# 6_cell_amplifier.net
KiCad netlist of a schematic drawn in Altium Designer
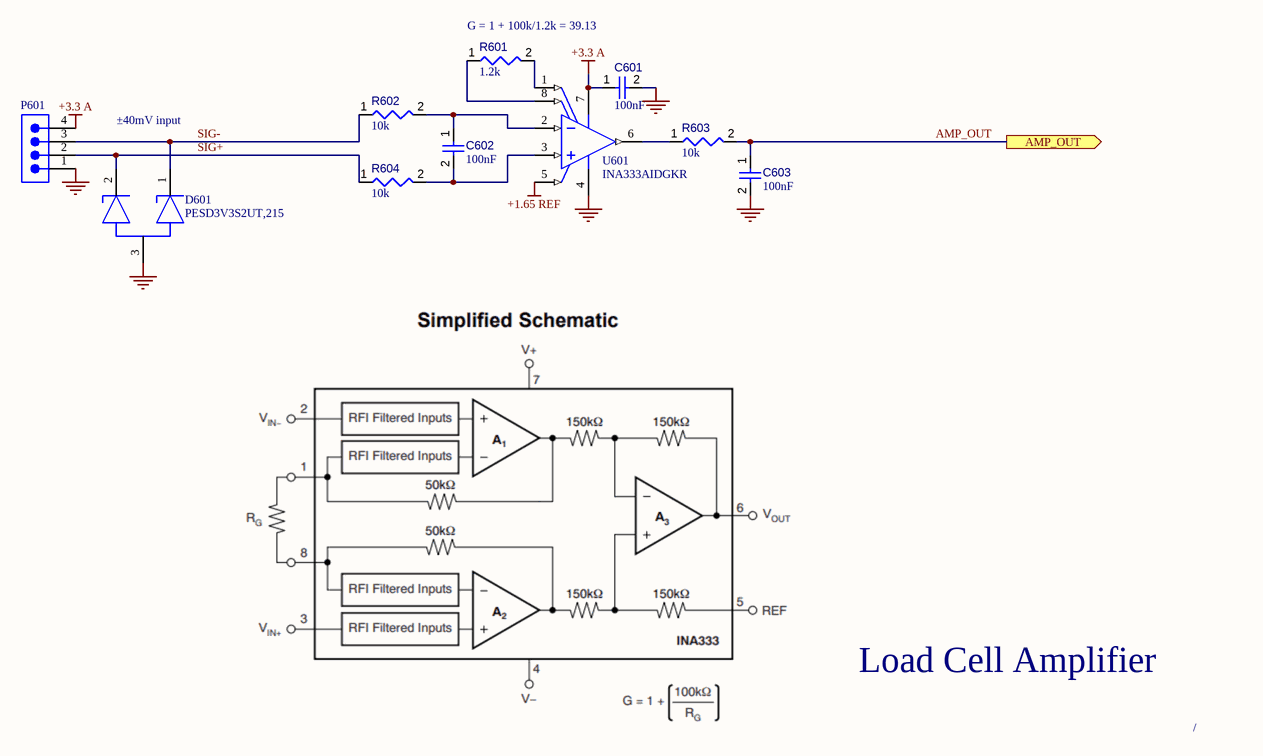
[diagram p0: 6 cell amplifier.SchDoc]

(export (version "E")
  (design (tool "Eeschema 10.0.6"))
  (components
    (comp (ref "C601")
      (value "100nF")
      (footprint "CAPC0402(1005)60_L")
      (description "Chip Capacitor, 100nF +/-20%, 25V, 0402, Thickness 0.6 mm")
      (fields (field (name "TOLERANCE") "10%") (field (name "Comment") "Capacitor 100nF +/-20% 25V 0402"))
      (libsource (lib "UBC Uncrewed Aircraft Systems") (part "CAP-NP-2"))
    )
    (comp (ref "C602")
      (value "100nF")
      (footprint "CAPC0402(1005)60_L")
      (description "Chip Capacitor, 100nF +/-20%, 25V, 0402, Thickness 0.6 mm")
      (fields (field (name "TOLERANCE") "10%") (field (name "Comment") "Capacitor 100nF +/-20% 25V 0402"))
      (libsource (lib "UBC Uncrewed Aircraft Systems") (part "CAP-NP-2"))
    )
    (comp (ref "C603")
      (value "100nF")
      (footprint "CAPC0402(1005)60_L")
      (description "Chip Capacitor, 100nF +/-20%, 25V, 0402, Thickness 0.6 mm")
      (fields (field (name "TOLERANCE") "10%") (field (name "Comment") "Capacitor 100nF +/-20% 25V 0402"))
      (libsource (lib "UBC Uncrewed Aircraft Systems") (part "CAP-NP-2"))
    )
    (comp (ref "D601")
      (value "PESD3V3S2UT,215")
      (footprint "FP-SOT23-IPC_A")
      (description "TVS DIODE 3.3VWM 20VC TO236AB")
      (libsource (lib "Altium Content Vault") (part "05bab3e457e9f60b0f1ca7a96343362"))
    )
    (comp (ref "P601")
      (value "61300411121")
      (footprint "61300411121")
      (libsource (lib "Altium Content Vault") (part "Header_Male_1R_04P"))
    )
    (comp (ref "R601")
      (value "1.2k")
      (footprint "RESC0402(1005)_L")
      (description "Chip Resistor, 1.2 kOhms, +/-1 %, 63 mW, -55 to 155 degC, 0402")
      (fields (field (name "TOLERANCE") "1%") (field (name "POWER") "63mW"))
      (libsource (lib "UBC Uncrewed Aircraft Systems") (part "RES-2"))
    )
    (comp (ref "R602")
      (value "10k")
      (footprint "RESC0402(1005)_L")
      (description "Chip Resistor, 10 kOhms, +/-1 %, 63 mW, -55 to 125 degC, 0402")
      (fields (field (name "POWER") "63mW") (field (name "TOLERANCE") "1%"))
      (libsource (lib "UBC Uncrewed Aircraft Systems") (part "RES-2"))
    )
    (comp (ref "R603")
      (value "10k")
      (footprint "RESC0402(1005)_L")
      (description "Chip Resistor, 10 kOhms, +/-1 %, 63 mW, -55 to 125 degC, 0402")
      (fields (field (name "POWER") "63mW") (field (name "TOLERANCE") "1%"))
      (libsource (lib "UBC Uncrewed Aircraft Systems") (part "RES-2"))
    )
    (comp (ref "R604")
      (value "10k")
      (footprint "RESC0402(1005)_L")
      (description "Chip Resistor, 10 kOhms, +/-1 %, 63 mW, -55 to 125 degC, 0402")
      (fields (field (name "POWER") "63mW") (field (name "TOLERANCE") "1%"))
      (libsource (lib "UBC Uncrewed Aircraft Systems") (part "RES-2"))
    )
    (comp (ref "U601")
      (value "INA333AIDGKR")
      (footprint "DGK0008A_L")
      (fields (field (name "MANUFACTURER") "Texas Instruments"))
      (libsource (lib "Altium Content Vault") (part "TI-INAXXXXXX8"))
    )
  )
  (nets
    (net (code "1") (name "+1.65 REF") (class "Default")
      (node (ref "U601") (pin "5") (pinfunction "REF_5") (pintype "input"))
    )
    (net (code "2") (name "+3.3 A") (class "Default")
      (node (ref "C601") (pin "1") (pinfunction "1_1") (pintype "passive"))
      (node (ref "P601") (pin "4") (pinfunction "4_4") (pintype "passive"))
      (node (ref "U601") (pin "7") (pinfunction "V+_7") (pintype "power_in"))
    )
    (net (code "3") (name "/AMP_OUT") (class "Default")
      (node (ref "C603") (pin "1") (pinfunction "1_1") (pintype "passive"))
      (node (ref "R603") (pin "2") (pinfunction "2_2") (pintype "passive"))
    )
    (net (code "4") (name "/SIG+") (class "Default")
      (node (ref "D601") (pin "2") (pinfunction "2_2") (pintype "passive"))
      (node (ref "P601") (pin "2") (pinfunction "2_2") (pintype "passive"))
      (node (ref "R604") (pin "1") (pinfunction "1_1") (pintype "passive"))
    )
    (net (code "5") (name "/SIG-") (class "Default")
      (node (ref "D601") (pin "1") (pinfunction "1_1") (pintype "passive"))
      (node (ref "P601") (pin "3") (pinfunction "3_3") (pintype "passive"))
      (node (ref "R602") (pin "1") (pinfunction "1_1") (pintype "passive"))
    )
    (net (code "6") (name "GND") (class "Default")
      (node (ref "C601") (pin "2") (pinfunction "2_2") (pintype "passive"))
      (node (ref "C603") (pin "2") (pinfunction "2_2") (pintype "passive"))
      (node (ref "D601") (pin "3") (pinfunction "3_3") (pintype "passive"))
      (node (ref "P601") (pin "1") (pinfunction "1_1") (pintype "passive"))
      (node (ref "U601") (pin "4") (pinfunction "V-_4") (pintype "power_in"))
    )
    (net (code "7") (name "Net-(R601-Pad1)") (class "Default")
      (node (ref "R601") (pin "1") (pinfunction "1_1") (pintype "passive"))
      (node (ref "U601") (pin "8") (pinfunction "RG_8") (pintype "input"))
    )
    (net (code "8") (name "Net-(R601-Pad2)") (class "Default")
      (node (ref "R601") (pin "2") (pinfunction "2_2") (pintype "passive"))
      (node (ref "U601") (pin "1") (pinfunction "RG_1") (pintype "input"))
    )
    (net (code "9") (name "Net-(U601-VIN+)") (class "Default")
      (node (ref "C602") (pin "2") (pinfunction "2_2") (pintype "passive"))
      (node (ref "R604") (pin "2") (pinfunction "2_2") (pintype "passive"))
      (node (ref "U601") (pin "3") (pinfunction "VIN+_3") (pintype "input"))
    )
    (net (code "10") (name "Net-(U601-VIN-)") (class "Default")
      (node (ref "C602") (pin "1") (pinfunction "1_1") (pintype "passive"))
      (node (ref "R602") (pin "2") (pinfunction "2_2") (pintype "passive"))
      (node (ref "U601") (pin "2") (pinfunction "VIN-_2") (pintype "input"))
    )
    (net (code "11") (name "Net-(U601-VOUT)") (class "Default")
      (node (ref "R603") (pin "1") (pinfunction "1_1") (pintype "passive"))
      (node (ref "U601") (pin "6") (pinfunction "VOUT_6") (pintype "output"))
    )
  )
)
